# Power_3V3.net
KiCad netlist of a schematic drawn in Altium Designer
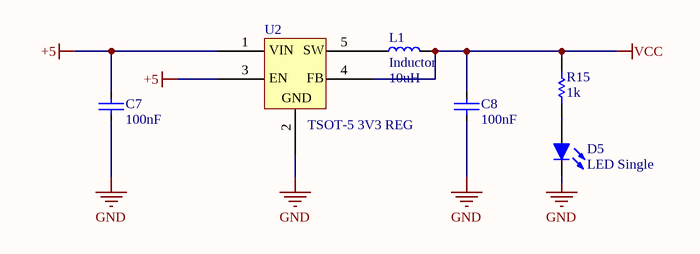
[diagram p0: Power 3V3.SchDoc]

(export (version "E")
  (design (tool "Eeschema 10.0.6"))
  (components
    (comp (ref "C7")
      (value "100nF")
      (footprint "C0603")
      (description "Capacitor Ceramic")
      (libsource (lib "RK_Lib") (part "Capacitor"))
    )
    (comp (ref "C8")
      (value "100nF")
      (footprint "C0603")
      (description "Capacitor Ceramic")
      (libsource (lib "RK_Lib") (part "Capacitor"))
    )
    (comp (ref "D5")
      (value "LED Single")
      (footprint "LED 0603")
      (description "LED")
      (libsource (lib "RK_Lib") (part "LED Single"))
    )
    (comp (ref "L1")
      (value "Inductor")
      (footprint "C1206")
      (fields (field (name "ALTIUM_VALUE") "10uH"))
      (libsource (lib "RK_Lib") (part "Inductor"))
    )
    (comp (ref "R15")
      (value "1k")
      (footprint "R 0603")
      (description "Resistor")
      (libsource (lib "RK_Lib") (part "Res"))
    )
    (comp (ref "U2")
      (value "TSOT-5 3V3 REG")
      (footprint "SOT-5 3V3 REG")
      (description "ANALOG DEVICES         ADP2108AUJZ-3.3-R7            STEP-DOWN DC/DC CONVERTER, TSOT-5")
      (fields
        (field (name "MANUFACTURER") "Analog Devices")
        (field (name "MANUFACTURER PART NUMBER") "ADP2108AUJZ-3.3-R7")
      )
      (libsource (lib "RK_Lib") (part "TSOT-5 3V3 REG"))
    )
  )
  (nets
    (net (code "1") (name "+5") (class "Default")
      (node (ref "C7") (pin "2") (pinfunction "2_2") (pintype "passive"))
      (node (ref "U2") (pin "1") (pinfunction "1_1") (pintype "passive"))
      (node (ref "U2") (pin "3") (pinfunction "3_3") (pintype "passive"))
    )
    (net (code "2") (name "GND") (class "Default")
      (node (ref "C7") (pin "1") (pinfunction "1_1") (pintype "passive"))
      (node (ref "C8") (pin "1") (pinfunction "1_1") (pintype "passive"))
      (node (ref "D5") (pin "2") (pinfunction "K_2") (pintype "passive"))
      (node (ref "U2") (pin "2") (pinfunction "2_2") (pintype "passive"))
    )
    (net (code "3") (name "Net-(D5-A)") (class "Default")
      (node (ref "D5") (pin "1") (pinfunction "A_1") (pintype "passive"))
      (node (ref "R15") (pin "1") (pinfunction "1_1") (pintype "passive"))
    )
    (net (code "4") (name "Net-(L1-Pad1)") (class "Default")
      (node (ref "L1") (pin "1") (pinfunction "1_1") (pintype "passive"))
      (node (ref "U2") (pin "5") (pinfunction "5_5") (pintype "passive"))
    )
    (net (code "5") (name "VCC") (class "Default")
      (node (ref "C8") (pin "2") (pinfunction "2_2") (pintype "passive"))
      (node (ref "L1") (pin "2") (pinfunction "2_2") (pintype "passive"))
      (node (ref "R15") (pin "2") (pinfunction "2_2") (pintype "passive"))
      (node (ref "U2") (pin "4") (pinfunction "4_4") (pintype "passive"))
    )
  )
)
